# Power_Supply.net
KiCad netlist of a schematic drawn in Altium Designer
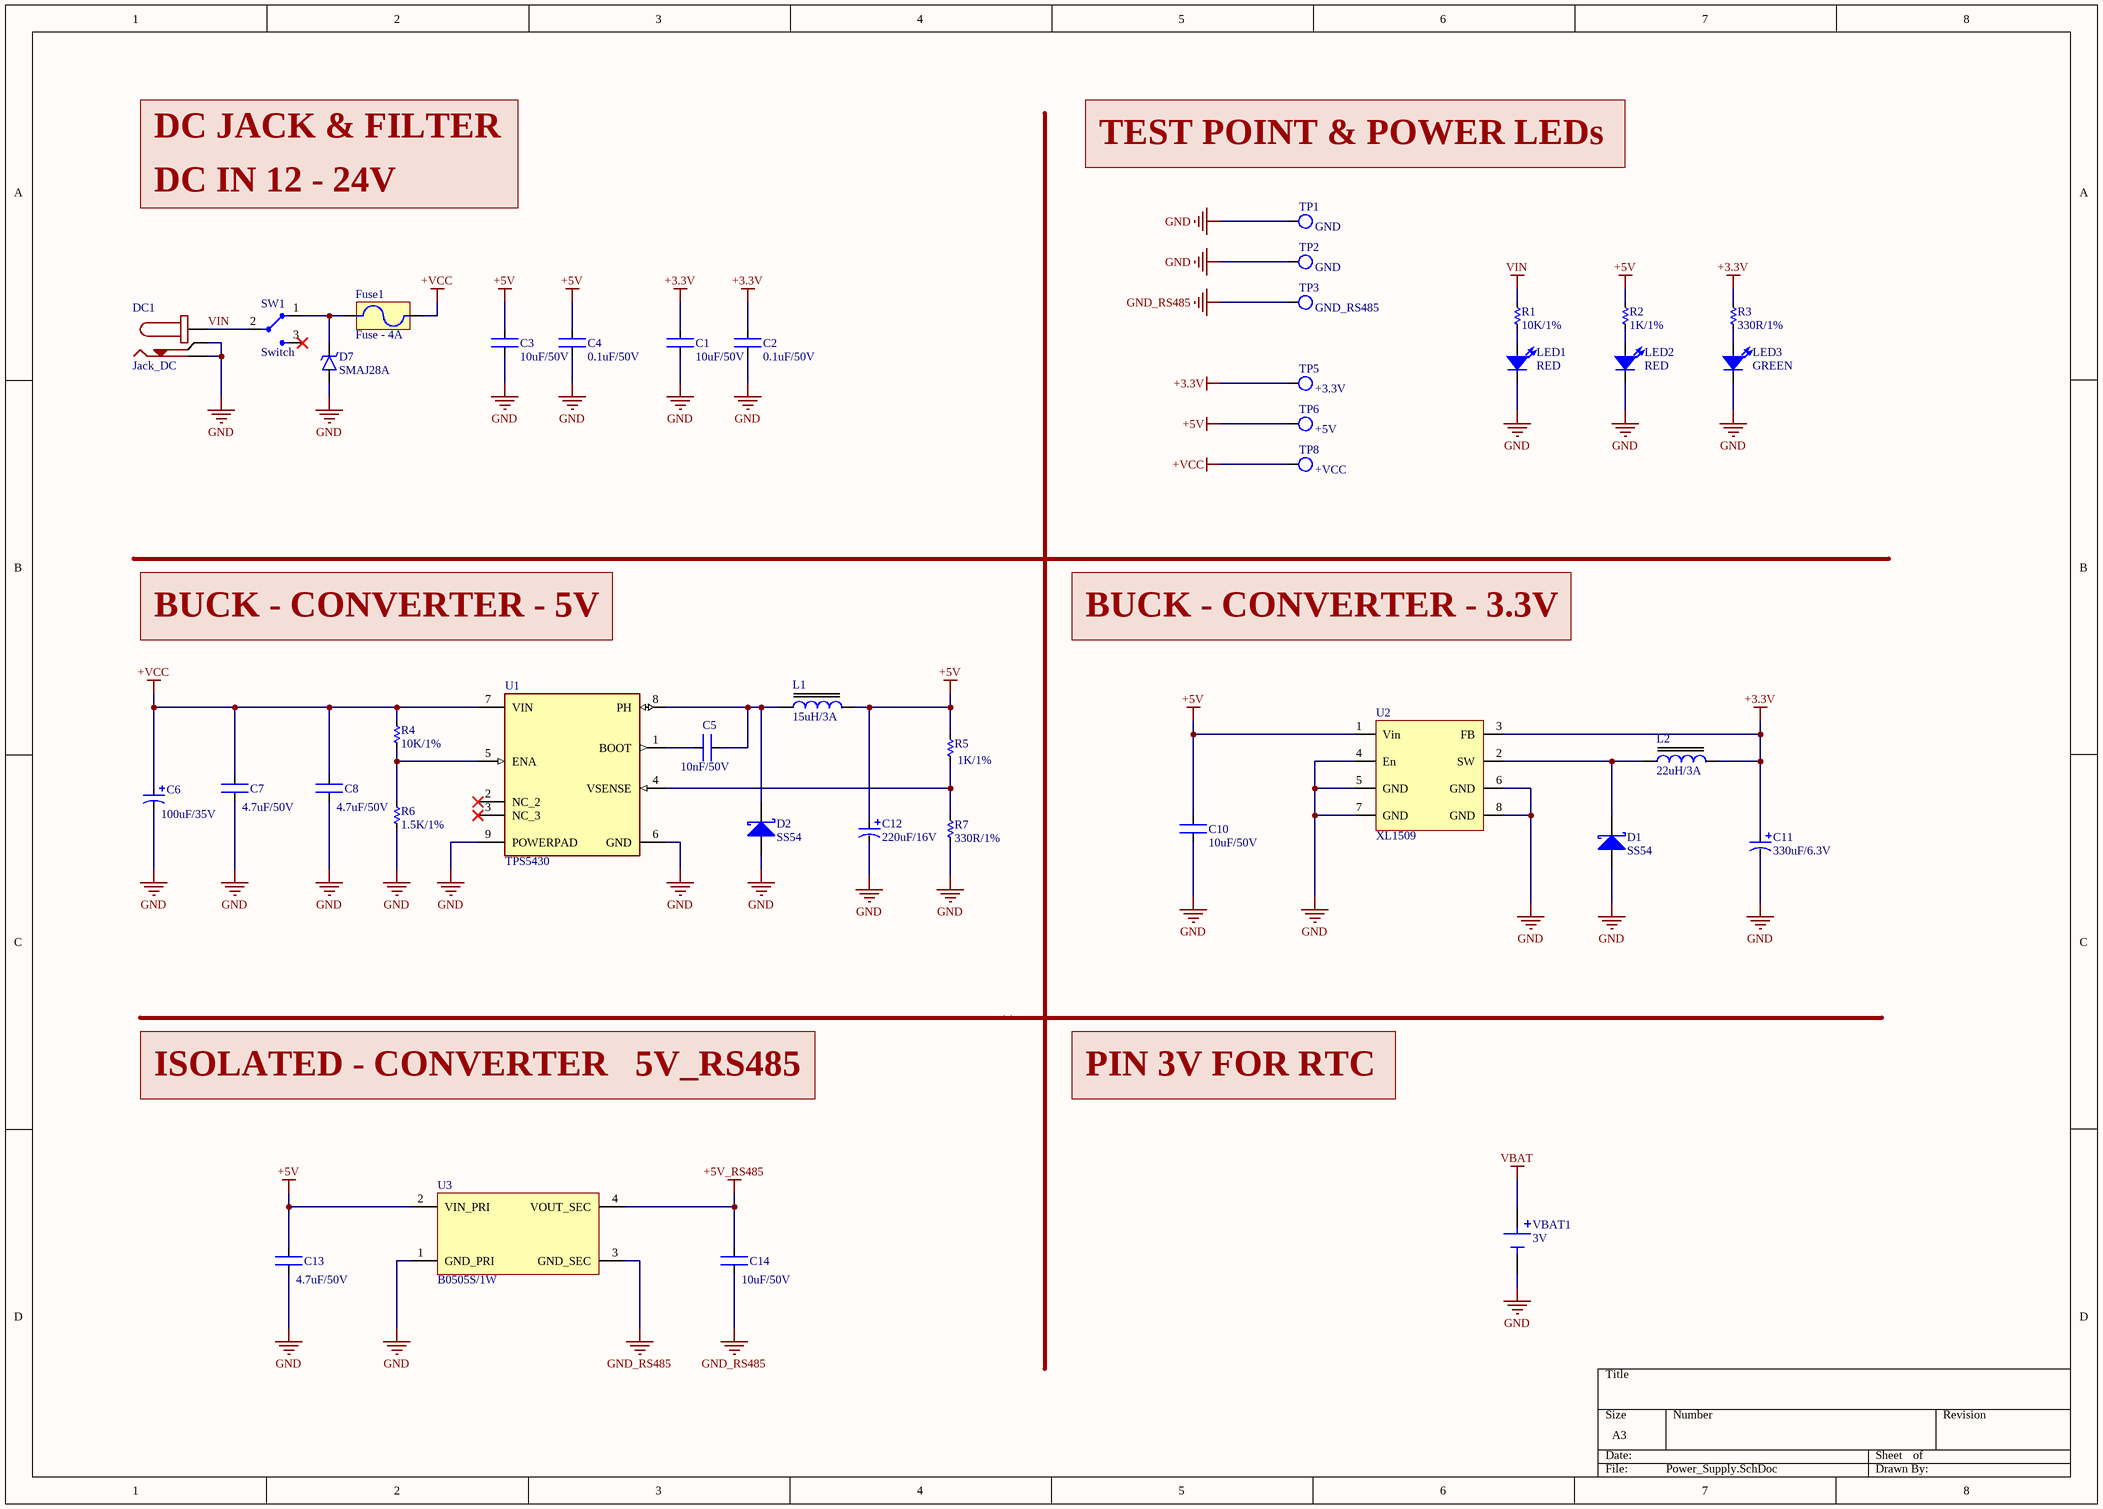
[diagram p0: Power_Supply.SchDoc]

(export (version "E")
  (design (tool "Eeschema 10.0.6"))
  (components
    (comp (ref "C1")
      (value "10uF/50V")
      (footprint "CAP - 0603")
      (description "CAPACITOR SMD - KEMET")
      (libsource (lib "NewLibrary") (part "CAPACITOR"))
    )
    (comp (ref "C2")
      (value "0.1uF/50V")
      (footprint "CAP - 0603")
      (description "CAPACITOR SMD - KEMET")
      (libsource (lib "NewLibrary") (part "CAPACITOR"))
    )
    (comp (ref "C3")
      (value "10uF/50V")
      (footprint "CAP - 0603")
      (description "CAPACITOR SMD - KEMET")
      (libsource (lib "NewLibrary") (part "CAPACITOR"))
    )
    (comp (ref "C4")
      (value "0.1uF/50V")
      (footprint "CAP - 0603")
      (description "CAPACITOR SMD - KEMET")
      (libsource (lib "NewLibrary") (part "CAPACITOR"))
    )
    (comp (ref "C5")
      (value "10nF/50V")
      (footprint "CAP - 0603")
      (description "CAPACITOR SMD - KEMET")
      (libsource (lib "NewLibrary") (part "CAPACITOR"))
    )
    (comp (ref "C6")
      (value "100uF/35V")
      (footprint "Alu_Cap_6.3_7.7")
      (libsource (lib "NewLibrary") (part "Alu_Capacitor"))
    )
    (comp (ref "C7")
      (value "4.7uF/50V")
      (footprint "CAP - 0603")
      (description "CAPACITOR SMD - KEMET")
      (libsource (lib "NewLibrary") (part "CAPACITOR"))
    )
    (comp (ref "C8")
      (value "4.7uF/50V")
      (footprint "CAP - 0603")
      (description "CAPACITOR SMD - KEMET")
      (libsource (lib "NewLibrary") (part "CAPACITOR"))
    )
    (comp (ref "C10")
      (value "10uF/50V")
      (footprint "CAP - 0603")
      (description "CAPACITOR SMD - KEMET")
      (libsource (lib "NewLibrary") (part "CAPACITOR"))
    )
    (comp (ref "C11")
      (value "330uF/6.3V")
      (footprint "Alu_Cap_6.3_7.7")
      (libsource (lib "NewLibrary") (part "Alu_Capacitor"))
    )
    (comp (ref "C12")
      (value "220uF/16V")
      (footprint "Alu_Cap_6.3_7.7")
      (libsource (lib "NewLibrary") (part "Alu_Capacitor"))
    )
    (comp (ref "C13")
      (value "4.7uF/50V")
      (footprint "CAP - 0603")
      (description "CAPACITOR SMD - KEMET")
      (libsource (lib "NewLibrary") (part "CAPACITOR"))
    )
    (comp (ref "C14")
      (value "10uF/50V")
      (footprint "CAP - 0603")
      (description "CAPACITOR SMD - KEMET")
      (libsource (lib "NewLibrary") (part "CAPACITOR"))
    )
    (comp (ref "D1")
      (value "SS54")
      (footprint "SS54")
      (description "DIODE SCHOTTKY 40V 5A SMA")
      (libsource (lib "NewLibrary") (part "SS54"))
    )
    (comp (ref "D2")
      (value "SS54")
      (footprint "SS54")
      (description "DIODE SCHOTTKY 40V 5A SMA")
      (libsource (lib "NewLibrary") (part "SS54"))
    )
    (comp (ref "D7")
      (value "SMAJ28A")
      (footprint "DO-214AC")
      (description "45.4V Clamp 8.8A Ipp Tvs diode surface mount")
      (libsource (lib "NewLibrary") (part "SMAJ28A"))
    )
    (comp (ref "DC1")
      (value "Jack_DC")
      (footprint "DC_5.5 x 2.1mm")
      (description "Jack DC IN (Hole)")
      (libsource (lib "NewLibrary") (part "Jack_DC"))
    )
    (comp (ref "Fuse1")
      (value "Fuse - 4A")
      (footprint "SMD-2")
      (description "Nano2 SMD FF submin fuse w/holder, 4A ¦ Littelfuse 0154004.DR")
      (libsource (lib "NewLibrary") (part "Fuse"))
    )
    (comp (ref "L1")
      (value "15uH/3A")
      (footprint "L_SMD_0630")
      (libsource (lib "NewLibrary") (part "Inductor_1_SMD"))
    )
    (comp (ref "L2")
      (value "22uH/3A")
      (footprint "L_SMD_0630")
      (libsource (lib "NewLibrary") (part "Inductor_1_SMD"))
    )
    (comp (ref "LED1")
      (value "RED")
      (footprint "RED_LED_0603")
      (description "LED SMD")
      (libsource (lib "NewLibrary") (part "LED_SMD"))
    )
    (comp (ref "LED2")
      (value "RED")
      (footprint "RED_LED_0603")
      (description "LED SMD")
      (libsource (lib "NewLibrary") (part "LED_SMD"))
    )
    (comp (ref "LED3")
      (value "GREEN")
      (footprint "GREEN_LED_0603")
      (description "LED SMD")
      (libsource (lib "NewLibrary") (part "LED_SMD"))
    )
    (comp (ref "R1")
      (value "10K/1%")
      (footprint "RES - 0603")
      (description "Resistor SMD - YAGEO")
      (libsource (lib "NewLibrary") (part "RESISTOR"))
    )
    (comp (ref "R2")
      (value "1K/1%")
      (footprint "RES - 0603")
      (description "Resistor SMD - YAGEO")
      (libsource (lib "NewLibrary") (part "RESISTOR"))
    )
    (comp (ref "R3")
      (value "330R/1%")
      (footprint "RES - 0603")
      (description "Resistor SMD - YAGEO")
      (libsource (lib "NewLibrary") (part "RESISTOR"))
    )
    (comp (ref "R4")
      (value "10K/1%")
      (footprint "RES - 0603")
      (description "Resistor SMD - YAGEO")
      (libsource (lib "NewLibrary") (part "RESISTOR"))
    )
    (comp (ref "R5")
      (value "1K/1%")
      (footprint "RES - 0603")
      (description "Resistor SMD - YAGEO")
      (libsource (lib "NewLibrary") (part "RESISTOR"))
    )
    (comp (ref "R6")
      (value "1.5K/1%")
      (footprint "RES - 0603")
      (description "Resistor SMD - YAGEO")
      (libsource (lib "NewLibrary") (part "RESISTOR"))
    )
    (comp (ref "R7")
      (value "330R/1%")
      (footprint "RES - 0603")
      (description "Resistor SMD - YAGEO")
      (libsource (lib "NewLibrary") (part "RESISTOR"))
    )
    (comp (ref "SW1")
      (value "Switch")
      (footprint "Dip_Switch_3_pins_0")
      (description "Switch 3 Pins")
      (libsource (lib "NewLibrary") (part "Switch"))
    )
    (comp (ref "TP1")
      (value "GND")
      (footprint "Test Point")
      (description "Test Point")
      (libsource (lib "NewLibrary") (part "TEST POINT"))
    )
    (comp (ref "TP2")
      (value "GND")
      (footprint "Test Point")
      (description "Test Point")
      (libsource (lib "NewLibrary") (part "TEST POINT"))
    )
    (comp (ref "TP3")
      (value "GND_RS485")
      (footprint "Test Point")
      (description "Test Point")
      (libsource (lib "NewLibrary") (part "TEST POINT"))
    )
    (comp (ref "TP5")
      (value "+3.3V")
      (footprint "Test Point")
      (description "Test Point")
      (libsource (lib "NewLibrary") (part "TEST POINT"))
    )
    (comp (ref "TP6")
      (value "+5V")
      (footprint "Test Point")
      (description "Test Point")
      (libsource (lib "NewLibrary") (part "TEST POINT"))
    )
    (comp (ref "TP8")
      (value "+VCC")
      (footprint "Test Point")
      (description "Test Point")
      (libsource (lib "NewLibrary") (part "TEST POINT"))
    )
    (comp (ref "U1")
      (value "TPS5430")
      (footprint "TPS5430")
      (description "Buck DC to DC Converter")
      (libsource (lib "NewLibrary") (part "TPS5430"))
    )
    (comp (ref "U2")
      (value "XL1509")
      (footprint "SOP_8")
      (description "Buck Converter")
      (libsource (lib "NewLibrary") (part "XL1509"))
    )
    (comp (ref "U3")
      (value "B0505S/1W")
      (footprint "B0505S/1W")
      (description "Isolated - Converter")
      (libsource (lib "NewLibrary") (part "B0505S/1W"))
    )
    (comp (ref "VBAT1")
      (value "3V")
      (footprint "CR2032 - SMD")
      (description "Battery Base CR2032")
      (libsource (lib "NewLibrary") (part "Battery Base"))
    )
  )
  (nets
    (net (code "1") (name "+3.3V") (class "Default")
      (node (ref "C1") (pin "1") (pinfunction "1_1") (pintype "passive"))
      (node (ref "C11") (pin "1") (pinfunction "1_1") (pintype "passive"))
      (node (ref "C2") (pin "1") (pinfunction "1_1") (pintype "passive"))
      (node (ref "L2") (pin "2") (pinfunction "5_2") (pintype "passive"))
      (node (ref "R3") (pin "1") (pinfunction "1_1") (pintype "passive"))
      (node (ref "TP5") (pin "1") (pinfunction "1_1") (pintype "passive"))
      (node (ref "U2") (pin "3") (pinfunction "FB_3") (pintype "passive"))
    )
    (net (code "2") (name "+5V") (class "Default")
      (node (ref "C10") (pin "1") (pinfunction "1_1") (pintype "passive"))
      (node (ref "C12") (pin "1") (pinfunction "1_1") (pintype "passive"))
      (node (ref "C13") (pin "1") (pinfunction "1_1") (pintype "passive"))
      (node (ref "C3") (pin "1") (pinfunction "1_1") (pintype "passive"))
      (node (ref "C4") (pin "1") (pinfunction "1_1") (pintype "passive"))
      (node (ref "L1") (pin "2") (pinfunction "5_2") (pintype "passive"))
      (node (ref "R2") (pin "1") (pinfunction "1_1") (pintype "passive"))
      (node (ref "R5") (pin "1") (pinfunction "1_1") (pintype "passive"))
      (node (ref "TP6") (pin "1") (pinfunction "1_1") (pintype "passive"))
      (node (ref "U2") (pin "1") (pinfunction "Vin_1") (pintype "passive"))
      (node (ref "U3") (pin "2") (pinfunction "VIN_PRI_2") (pintype "passive"))
    )
    (net (code "3") (name "+5V_RS485") (class "Default")
      (node (ref "C14") (pin "1") (pinfunction "1_1") (pintype "passive"))
      (node (ref "U3") (pin "4") (pinfunction "VOUT_SEC_4") (pintype "passive"))
    )
    (net (code "4") (name "+VCC") (class "Default")
      (node (ref "C6") (pin "1") (pinfunction "1_1") (pintype "passive"))
      (node (ref "C7") (pin "1") (pinfunction "1_1") (pintype "passive"))
      (node (ref "C8") (pin "1") (pinfunction "1_1") (pintype "passive"))
      (node (ref "Fuse1") (pin "2") (pinfunction "2_2") (pintype "passive"))
      (node (ref "R4") (pin "1") (pinfunction "1_1") (pintype "passive"))
      (node (ref "TP8") (pin "1") (pinfunction "1_1") (pintype "passive"))
      (node (ref "U1") (pin "7") (pinfunction "VIN_7") (pintype "power_in"))
    )
    (net (code "5") (name "GND") (class "Default")
      (node (ref "C1") (pin "2") (pinfunction "2_2") (pintype "passive"))
      (node (ref "C10") (pin "2") (pinfunction "2_2") (pintype "passive"))
      (node (ref "C11") (pin "2") (pinfunction "2_2") (pintype "passive"))
      (node (ref "C12") (pin "2") (pinfunction "2_2") (pintype "passive"))
      (node (ref "C13") (pin "2") (pinfunction "2_2") (pintype "passive"))
      (node (ref "C2") (pin "2") (pinfunction "2_2") (pintype "passive"))
      (node (ref "C3") (pin "2") (pinfunction "2_2") (pintype "passive"))
      (node (ref "C4") (pin "2") (pinfunction "2_2") (pintype "passive"))
      (node (ref "C6") (pin "2") (pinfunction "2_2") (pintype "passive"))
      (node (ref "C7") (pin "2") (pinfunction "2_2") (pintype "passive"))
      (node (ref "C8") (pin "2") (pinfunction "2_2") (pintype "passive"))
      (node (ref "D1") (pin "1") (pinfunction "A_1") (pintype "passive"))
      (node (ref "D2") (pin "1") (pinfunction "A_1") (pintype "passive"))
      (node (ref "D7") (pin "A") (pinfunction "A_A") (pintype "passive"))
      (node (ref "DC1") (pin "2") (pinfunction "TN_2") (pintype "passive"))
      (node (ref "DC1") (pin "3") (pinfunction "T_3") (pintype "passive"))
      (node (ref "LED1") (pin "2") (pinfunction "2_2") (pintype "passive"))
      (node (ref "LED2") (pin "2") (pinfunction "2_2") (pintype "passive"))
      (node (ref "LED3") (pin "2") (pinfunction "2_2") (pintype "passive"))
      (node (ref "R6") (pin "2") (pinfunction "2_2") (pintype "passive"))
      (node (ref "R7") (pin "2") (pinfunction "2_2") (pintype "passive"))
      (node (ref "TP1") (pin "1") (pinfunction "1_1") (pintype "passive"))
      (node (ref "TP2") (pin "1") (pinfunction "1_1") (pintype "passive"))
      (node (ref "U1") (pin "6") (pinfunction "GND_6") (pintype "passive"))
      (node (ref "U1") (pin "9") (pinfunction "POWERPAD_9") (pintype "passive"))
      (node (ref "U2") (pin "4") (pinfunction "En_4") (pintype "passive"))
      (node (ref "U2") (pin "5") (pinfunction "GND_5") (pintype "passive"))
      (node (ref "U2") (pin "6") (pinfunction "GND_6") (pintype "passive"))
      (node (ref "U2") (pin "7") (pinfunction "GND_7") (pintype "passive"))
      (node (ref "U2") (pin "8") (pinfunction "GND_8") (pintype "passive"))
      (node (ref "U3") (pin "1") (pinfunction "GND_PRI_1") (pintype "passive"))
      (node (ref "VBAT1") (pin "N") (pinfunction "NEG_N") (pintype "passive"))
    )
    (net (code "6") (name "GND_RS485") (class "Default")
      (node (ref "C14") (pin "2") (pinfunction "2_2") (pintype "passive"))
      (node (ref "TP3") (pin "1") (pinfunction "1_1") (pintype "passive"))
      (node (ref "U3") (pin "3") (pinfunction "GND_SEC_3") (pintype "passive"))
    )
    (net (code "7") (name "Net-(D1-K)") (class "Default")
      (node (ref "D1") (pin "2") (pinfunction "K_2") (pintype "passive"))
      (node (ref "L2") (pin "1") (pinfunction "4_1") (pintype "passive"))
      (node (ref "U2") (pin "2") (pinfunction "SW_2") (pintype "passive"))
    )
    (net (code "8") (name "Net-(D2-K)") (class "Default")
      (node (ref "C5") (pin "2") (pinfunction "2_2") (pintype "passive"))
      (node (ref "D2") (pin "2") (pinfunction "K_2") (pintype "passive"))
      (node (ref "L1") (pin "1") (pinfunction "4_1") (pintype "passive"))
      (node (ref "U1") (pin "8") (pinfunction "PH_8") (pintype "bidirectional"))
    )
    (net (code "9") (name "Net-(D7-PadC)") (class "Default")
      (node (ref "D7") (pin "C") (pinfunction "C_C") (pintype "passive"))
      (node (ref "Fuse1") (pin "1") (pinfunction "1_1") (pintype "passive"))
      (node (ref "SW1") (pin "1") (pintype "passive"))
    )
    (net (code "10") (name "Net-(LED1-Pad1)") (class "Default")
      (node (ref "LED1") (pin "1") (pinfunction "1_1") (pintype "passive"))
      (node (ref "R1") (pin "2") (pinfunction "2_2") (pintype "passive"))
    )
    (net (code "11") (name "Net-(LED2-Pad1)") (class "Default")
      (node (ref "LED2") (pin "1") (pinfunction "1_1") (pintype "passive"))
      (node (ref "R2") (pin "2") (pinfunction "2_2") (pintype "passive"))
    )
    (net (code "12") (name "Net-(LED3-Pad1)") (class "Default")
      (node (ref "LED3") (pin "1") (pinfunction "1_1") (pintype "passive"))
      (node (ref "R3") (pin "2") (pinfunction "2_2") (pintype "passive"))
    )
    (net (code "13") (name "Net-(U1-BOOT)") (class "Default")
      (node (ref "C5") (pin "1") (pinfunction "1_1") (pintype "passive"))
      (node (ref "U1") (pin "1") (pinfunction "BOOT_1") (pintype "output"))
    )
    (net (code "14") (name "Net-(U1-ENA)") (class "Default")
      (node (ref "R4") (pin "2") (pinfunction "2_2") (pintype "passive"))
      (node (ref "R6") (pin "1") (pinfunction "1_1") (pintype "passive"))
      (node (ref "U1") (pin "5") (pinfunction "ENA_5") (pintype "input"))
    )
    (net (code "15") (name "Net-(U1-VSENSE)") (class "Default")
      (node (ref "R5") (pin "2") (pinfunction "2_2") (pintype "passive"))
      (node (ref "R7") (pin "1") (pinfunction "1_1") (pintype "passive"))
      (node (ref "U1") (pin "4") (pinfunction "VSENSE_4") (pintype "input"))
    )
    (net (code "16") (name "VBAT") (class "Default")
      (node (ref "VBAT1") (pin "P") (pinfunction "POS_P") (pintype "passive"))
    )
    (net (code "17") (name "VIN") (class "Default")
      (node (ref "DC1") (pin "1") (pinfunction "S_1") (pintype "power_in"))
      (node (ref "R1") (pin "1") (pinfunction "1_1") (pintype "passive"))
      (node (ref "SW1") (pin "2") (pintype "passive"))
    )
    (net (code "18") (name "unconnected-(SW1-I{slash}O2-Pad3)") (class "Default")
      (node (ref "SW1") (pin "3") (pinfunction "I/O2_3") (pintype "passive+no_connect"))
    )
    (net (code "19") (name "unconnected-(U1-NC_2-Pad2)") (class "Default")
      (node (ref "U1") (pin "2") (pinfunction "NC_2_2") (pintype "passive+no_connect"))
    )
    (net (code "20") (name "unconnected-(U1-NC_3-Pad3)") (class "Default")
      (node (ref "U1") (pin "3") (pinfunction "NC_3_3") (pintype "passive+no_connect"))
    )
  )
)
